# FREENFET.net
KiCad netlist of a schematic drawn in EAGLE
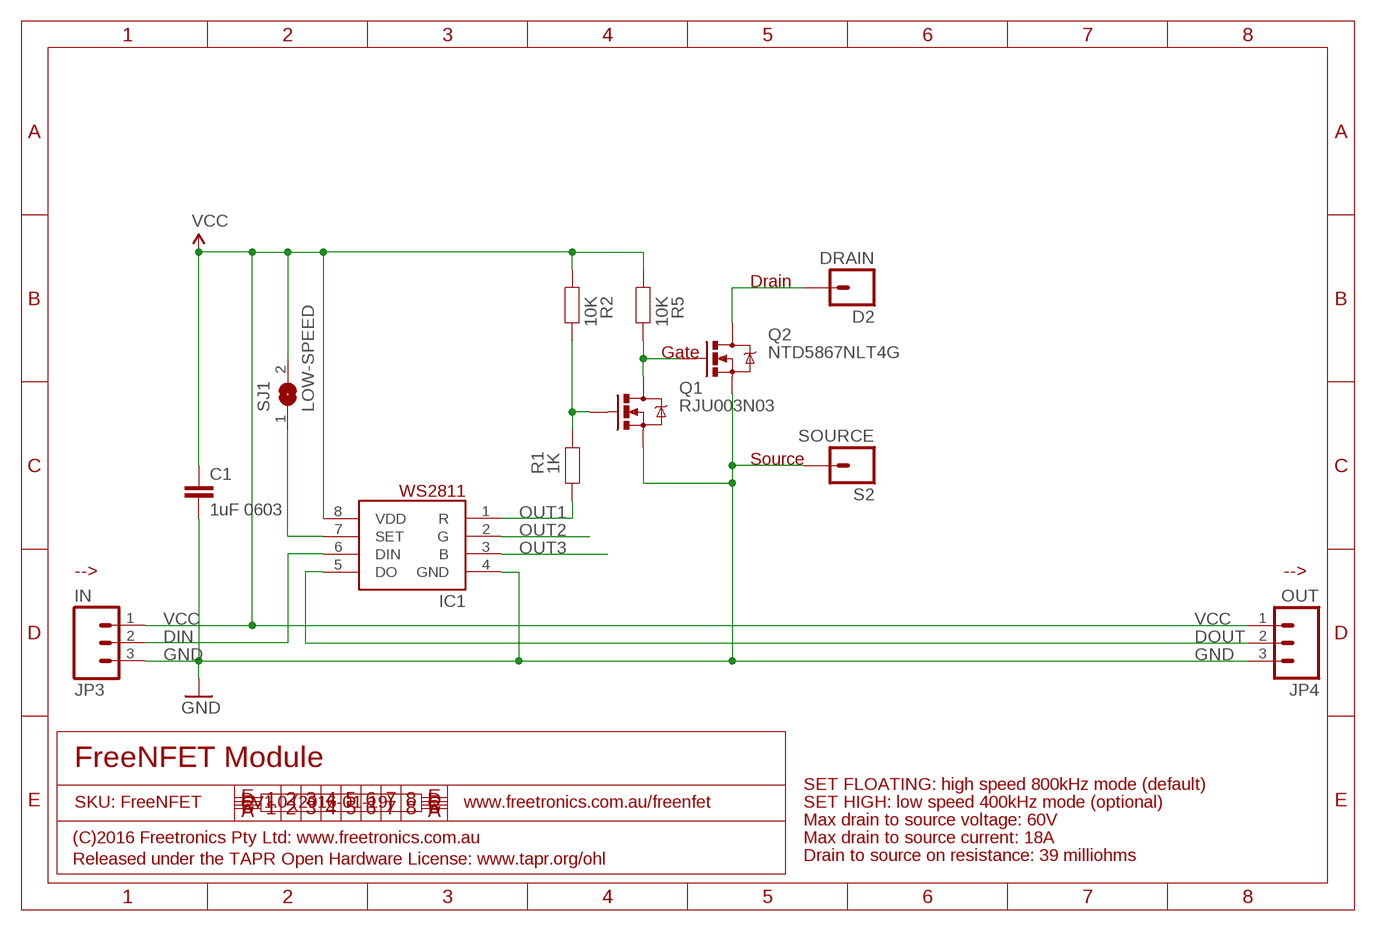
[diagram p0: schematic, sheet 1]

(export (version "E")
  (design (tool "Eeschema 10.0.6"))
  (components
    (comp (ref "C1")
      (value "1uF 0603")
      (footprint "eagle-import:0603")
      (libsource (lib "eagle-import") (part "CAP0603"))
    )
    (comp (ref "D2")
      (value "DRAIN")
      (footprint "eagle-import:1X01LARGE")
      (libsource (lib "eagle-import") (part "M01PTH_LARGE"))
    )
    (comp (ref "IC1")
      (value "WS2811-SOP8")
      (footprint "eagle-import:SO08-SKINNYPADS")
      (libsource (lib "eagle-import") (part "WS2811-SOP8"))
    )
    (comp (ref "JP3")
      (value "IN")
      (footprint "eagle-import:1X03")
      (libsource (lib "eagle-import") (part "M03PTH"))
    )
    (comp (ref "JP4")
      (value "OUT")
      (footprint "eagle-import:1X03")
      (libsource (lib "eagle-import") (part "M03PTH"))
    )
    (comp (ref "Q1")
      (value "RJU003N03")
      (footprint "eagle-import:SOT32-3")
      (libsource (lib "eagle-import") (part "MOSFET-NSOT-323"))
    )
    (comp (ref "Q2")
      (value "NTD5867NLT4G")
      (footprint "eagle-import:DPACK")
      (libsource (lib "eagle-import") (part "MOSFET-NCHANNELDPAK"))
    )
    (comp (ref "R1")
      (value "1K")
      (footprint "eagle-import:0603")
      (libsource (lib "eagle-import") (part "RESISTOR0603"))
    )
    (comp (ref "R2")
      (value "10K")
      (footprint "eagle-import:0603")
      (libsource (lib "eagle-import") (part "RESISTOR0603"))
    )
    (comp (ref "R5")
      (value "10K")
      (footprint "eagle-import:0603")
      (libsource (lib "eagle-import") (part "RESISTOR0603"))
    )
    (comp (ref "S2")
      (value "SOURCE")
      (footprint "eagle-import:1X01LARGE")
      (libsource (lib "eagle-import") (part "M01PTH_LARGE"))
    )
    (comp (ref "SJ1")
      (value "LOW-SPEED")
      (footprint "eagle-import:SJ")
      (libsource (lib "eagle-import") (part "SJN"))
    )
  )
  (nets
    (net (code "1") (name "/DIN") (class "Default")
      (node (ref "IC1") (pin "6") (pinfunction "DIN_6") (pintype "input"))
      (node (ref "JP3") (pin "2") (pinfunction "2_2") (pintype "passive"))
    )
    (net (code "2") (name "/DOUT") (class "Default")
      (node (ref "IC1") (pin "5") (pinfunction "DO_5") (pintype "output"))
      (node (ref "JP4") (pin "2") (pinfunction "2_2") (pintype "passive"))
    )
    (net (code "3") (name "/OUT1") (class "Default")
      (node (ref "IC1") (pin "1") (pinfunction "R_1") (pintype "open_collector"))
      (node (ref "R1") (pin "2") (pinfunction "2_2") (pintype "passive"))
    )
    (net (code "4") (name "/OUT2") (class "Default")
      (node (ref "IC1") (pin "2") (pinfunction "G_2") (pintype "open_collector"))
    )
    (net (code "5") (name "/OUT3") (class "Default")
      (node (ref "IC1") (pin "3") (pinfunction "B_3") (pintype "open_collector"))
    )
    (net (code "6") (name "GND") (class "Default")
      (node (ref "C1") (pin "2") (pinfunction "2_2") (pintype "passive"))
      (node (ref "IC1") (pin "4") (pinfunction "GND_4") (pintype "power_in"))
      (node (ref "JP3") (pin "3") (pinfunction "3_3") (pintype "passive"))
      (node (ref "JP4") (pin "3") (pinfunction "3_3") (pintype "passive"))
      (node (ref "Q1") (pin "2") (pinfunction "S_2") (pintype "passive"))
      (node (ref "Q2") (pin "3") (pinfunction "S_3") (pintype "passive"))
      (node (ref "S2") (pin "1") (pinfunction "1_1") (pintype "passive"))
    )
    (net (code "7") (name "Net-(IC1-SET)") (class "Default")
      (node (ref "IC1") (pin "7") (pinfunction "SET_7") (pintype "input"))
      (node (ref "SJ1") (pin "1") (pinfunction "1_1") (pintype "passive"))
    )
    (net (code "8") (name "Net-(Q1-D)") (class "Default")
      (node (ref "Q1") (pin "3") (pinfunction "D_3") (pintype "passive"))
      (node (ref "Q2") (pin "1") (pinfunction "G_1") (pintype "passive"))
      (node (ref "R5") (pin "1") (pinfunction "1_1") (pintype "passive"))
    )
    (net (code "9") (name "Net-(Q1-G)") (class "Default")
      (node (ref "Q1") (pin "1") (pinfunction "G_1") (pintype "passive"))
      (node (ref "R1") (pin "1") (pinfunction "1_1") (pintype "passive"))
      (node (ref "R2") (pin "1") (pinfunction "1_1") (pintype "passive"))
    )
    (net (code "10") (name "Net-(Q2-D)") (class "Default")
      (node (ref "D2") (pin "1") (pinfunction "1_1") (pintype "passive"))
      (node (ref "Q2") (pin "2") (pinfunction "D_2") (pintype "passive"))
    )
    (net (code "11") (name "VCC") (class "Default")
      (node (ref "C1") (pin "1") (pinfunction "1_1") (pintype "passive"))
      (node (ref "IC1") (pin "8") (pinfunction "VDD_8") (pintype "power_in"))
      (node (ref "JP3") (pin "1") (pinfunction "1_1") (pintype "passive"))
      (node (ref "JP4") (pin "1") (pinfunction "1_1") (pintype "passive"))
      (node (ref "R2") (pin "2") (pinfunction "2_2") (pintype "passive"))
      (node (ref "R5") (pin "2") (pinfunction "2_2") (pintype "passive"))
      (node (ref "SJ1") (pin "2") (pinfunction "2_2") (pintype "passive"))
    )
  )
)
